# MCED_Controller.net
KiCad netlist of a schematic drawn in Altium Designer
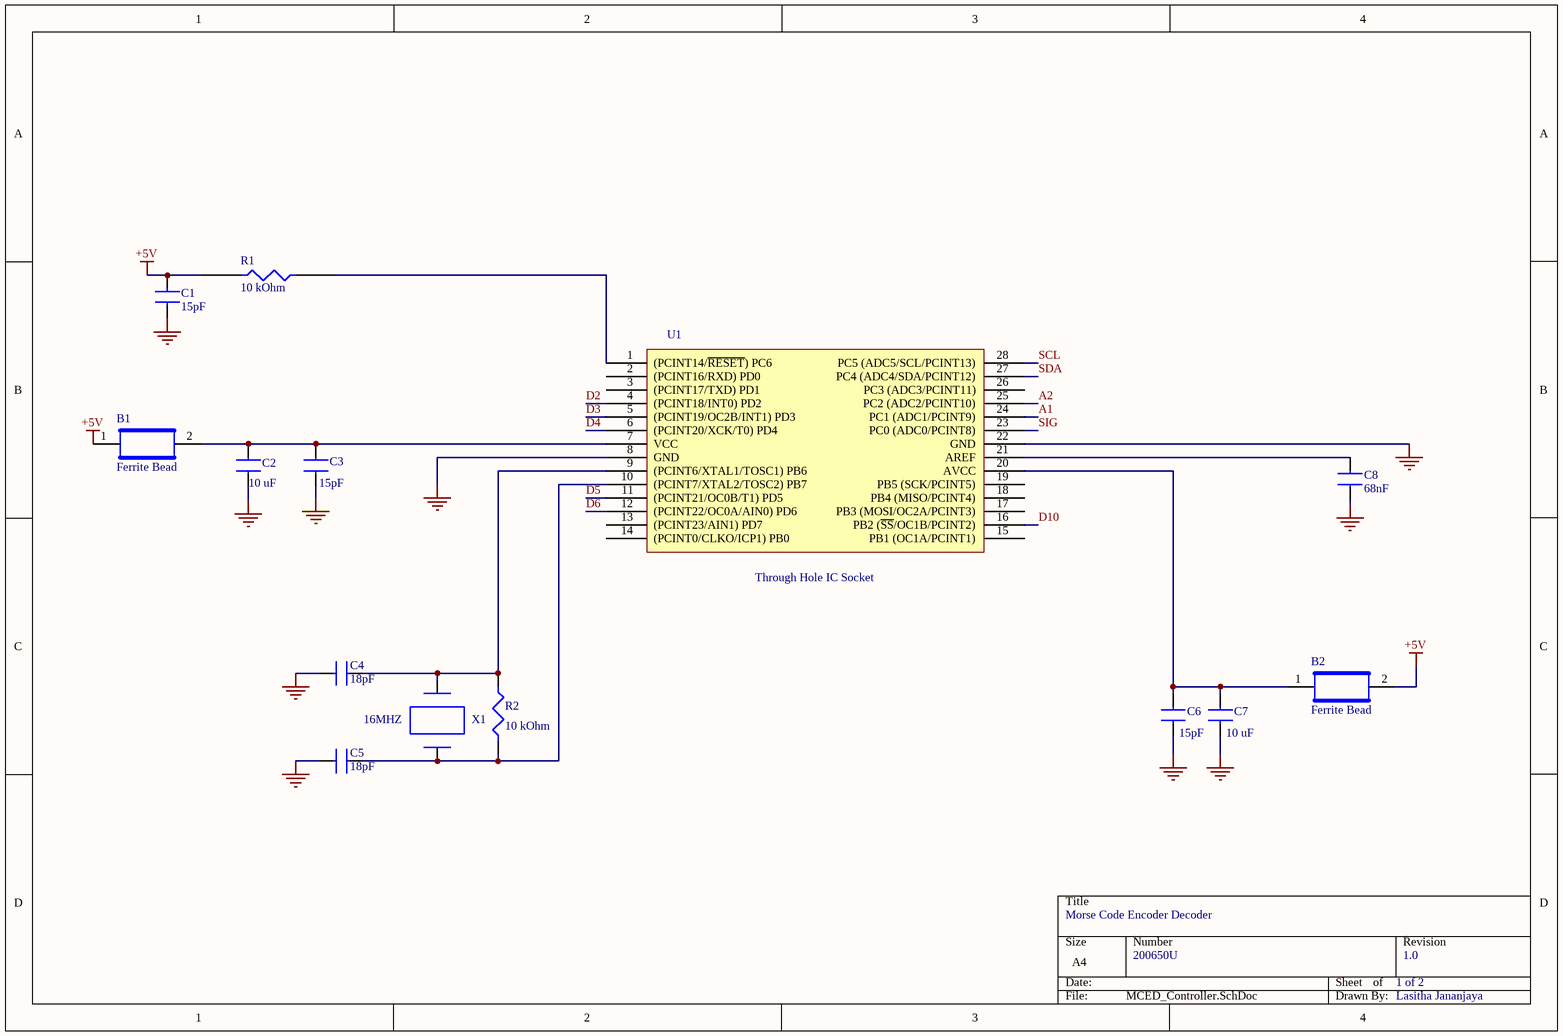
[diagram p0: MCED_Controller.SchDoc]

(export (version "E")
  (design (tool "Eeschema 10.0.6"))
  (components
    (comp (ref "B1")
      (value "Ferrite Bead")
      (footprint "FERRITE BEAD C2012X105N")
      (description "Ferrite Bead, 1 Function(s), 2A")
      (fields
        (field (name "MANUFACTURER") "TDK")
        (field (name "MANUFACTURER PART NUMBER") "MPZ2012S601AT000")
      )
      (libsource (lib "MCED_Schlib") (part "MPZ2012S601AT000"))
    )
    (comp (ref "B2")
      (value "Ferrite Bead")
      (footprint "FERRITE BEAD C2012X105N")
      (description "Ferrite Bead, 1 Function(s), 2A")
      (fields
        (field (name "MANUFACTURER") "TDK")
        (field (name "MANUFACTURER PART NUMBER") "MPZ2012S601AT000")
      )
      (libsource (lib "MCED_Schlib") (part "MPZ2012S601AT000"))
    )
    (comp (ref "C1")
      (value "15pF")
      (footprint "C0805")
      (fields
        (field (name "MANUFACTURER") "Vishay Vitramon")
        (field (name "MANUFACTURER PART NUMBER") "VJ0805A220GXACW1BC")
      )
      (libsource (lib "MCED_Schlib") (part "VJ0805A220GXACW1BC"))
    )
    (comp (ref "C2")
      (value "10 uF")
      (footprint "C0805")
      (fields
        (field (name "MANUFACTURER") "Samsung")
        (field (name "MANUFACTURER PART NUMBER") "CL21A106KBYQNNE")
      )
      (libsource (lib "MCED_Schlib") (part "CL21A106KBYQNNE"))
    )
    (comp (ref "C3")
      (value "15pF")
      (footprint "C0805")
      (fields
        (field (name "MANUFACTURER") "Vishay Vitramon")
        (field (name "MANUFACTURER PART NUMBER") "VJ0805A220GXACW1BC")
      )
      (libsource (lib "MCED_Schlib") (part "VJ0805A220GXACW1BC"))
    )
    (comp (ref "C4")
      (value "18pF")
      (footprint "C0805")
      (fields
        (field (name "MANUFACTURER") "Vishay Vitramon")
        (field (name "MANUFACTURER PART NUMBER") "VJ0805A220GXACW1BC")
      )
      (libsource (lib "MCED_Schlib") (part "VJ0805A220GXACW1BC"))
    )
    (comp (ref "C5")
      (value "18pF")
      (footprint "C0805")
      (fields
        (field (name "MANUFACTURER") "Vishay Vitramon")
        (field (name "MANUFACTURER PART NUMBER") "VJ0805A220GXACW1BC")
      )
      (libsource (lib "MCED_Schlib") (part "VJ0805A220GXACW1BC"))
    )
    (comp (ref "C6")
      (value "15pF")
      (footprint "C0805")
      (fields
        (field (name "MANUFACTURER") "Vishay Vitramon")
        (field (name "MANUFACTURER PART NUMBER") "VJ0805A220GXACW1BC")
      )
      (libsource (lib "MCED_Schlib") (part "VJ0805A220GXACW1BC"))
    )
    (comp (ref "C7")
      (value "10 uF")
      (footprint "C0805")
      (fields
        (field (name "MANUFACTURER") "Samsung")
        (field (name "MANUFACTURER PART NUMBER") "CL21A106KBYQNNE")
      )
      (libsource (lib "MCED_Schlib") (part "CL21A106KBYQNNE"))
    )
    (comp (ref "C8")
      (value "68nF")
      (footprint "C0805")
      (fields
        (field (name "MANUFACTURER") "Samsung")
        (field (name "MANUFACTURER PART NUMBER") "CL21A106KBYQNNE")
      )
      (libsource (lib "MCED_Schlib") (part "CL21A106KBYQNNE"))
    )
    (comp (ref "R1")
      (value "10 kOhm")
      (footprint "10K")
      (description "10 kOhm, Fixed Resistor, Thin Film, 0.2W, 10000ohm, 150V, 0.5% +/-Tol, -25,25ppm/Cel, 0805")
      (fields
        (field (name "MANUFACTURER") "Vishay Beyschlag")
        (field (name "MANUFACTURER PART NUMBER") "MCU0805MD1002DP500")
      )
      (libsource (lib "") (part "MCU0805MD1002DP500_1"))
    )
    (comp (ref "R2")
      (value "10 kOhm")
      (footprint "10K")
      (description "10 kOhm, Fixed Resistor, Thin Film, 0.2W, 10000ohm, 150V, 0.5% +/-Tol, -25,25ppm/Cel, 0805")
      (fields
        (field (name "MANUFACTURER") "Vishay Beyschlag")
        (field (name "MANUFACTURER PART NUMBER") "MCU0805MD1002DP500")
      )
      (libsource (lib "MCED_Schlib") (part "MCU0805MD1002DP500"))
    )
    (comp (ref "U1")
      (value "Through Hole IC Socket")
      (footprint "28dip_through_hole_ic_socket")
      (description "Through Hole IC Sockets 28P / .300\"")
      (fields
        (field (name "MANUFACTURER") "Adam Equipment")
        (field (name "MANUFACTURER PART NUMBER") "ICS-328-T")
      )
      (libsource (lib "MCED_Schlib") (part "ICS-328-T"))
    )
    (comp (ref "X1")
      (value "16MHZ")
      (footprint "ABLS-16.000MHZ-B4-T_CRYSTAL")
      (description "16MHz ±30ppm 晶体 18pF 40 欧姆 -20°C ~ 70°C  表面贴装 HC49/US")
      (fields
        (field (name "MANUFACTURER") "Abracon")
        (field (name "MANUFACTURER PART NUMBER") "ABLS-16.000MHZ-B4-T")
      )
      (libsource (lib "MCED_Schlib") (part "ABLS-16.000MHZ-B4-T"))
    )
  )
  (nets
    (net (code "1") (name "+5V") (class "Default")
      (node (ref "B1") (pin "1") (pinfunction "1_1") (pintype "passive"))
      (node (ref "B2") (pin "2") (pinfunction "2_2") (pintype "passive"))
      (node (ref "C1") (pin "2") (pinfunction "2_2") (pintype "passive"))
      (node (ref "R1") (pin "2") (pinfunction "2_2") (pintype "passive"))
    )
    (net (code "2") (name "/A1") (class "Default")
      (node (ref "U1") (pin "24") (pinfunction "PC1_(ADC1/PCINT9)_24") (pintype "passive"))
    )
    (net (code "3") (name "/A2") (class "Default")
      (node (ref "U1") (pin "25") (pinfunction "PC2_(ADC2/PCINT10)_25") (pintype "passive"))
    )
    (net (code "4") (name "/D2") (class "Default")
      (node (ref "U1") (pin "4") (pinfunction "(PCINT18/INT0)_PD2_4") (pintype "passive"))
    )
    (net (code "5") (name "/D3") (class "Default")
      (node (ref "U1") (pin "5") (pinfunction "(PCINT19/OC2B/INT1)_PD3_5") (pintype "passive"))
    )
    (net (code "6") (name "/D4") (class "Default")
      (node (ref "U1") (pin "6") (pinfunction "(PCINT20/XCK/T0)_PD4_6") (pintype "passive"))
    )
    (net (code "7") (name "/D5") (class "Default")
      (node (ref "U1") (pin "11") (pinfunction "(PCINT21/OC0B/T1)_PD5_11") (pintype "passive"))
    )
    (net (code "8") (name "/D6") (class "Default")
      (node (ref "U1") (pin "12") (pinfunction "(PCINT22/OC0A/AIN0)_PD6_12") (pintype "passive"))
    )
    (net (code "9") (name "/D10") (class "Default")
      (node (ref "U1") (pin "16") (pinfunction "PB2_(~{SS}/OC1B/PCINT2)_16") (pintype "passive"))
    )
    (net (code "10") (name "/SCL") (class "Default")
      (node (ref "U1") (pin "28") (pinfunction "PC5_(ADC5/SCL/PCINT13)_28") (pintype "passive"))
    )
    (net (code "11") (name "/SDA") (class "Default")
      (node (ref "U1") (pin "27") (pinfunction "PC4_(ADC4/SDA/PCINT12)_27") (pintype "passive"))
    )
    (net (code "12") (name "/SIG") (class "Default")
      (node (ref "U1") (pin "23") (pinfunction "PC0_(ADC0/PCINT8)_23") (pintype "passive"))
    )
    (net (code "13") (name "GND") (class "Default")
      (node (ref "C1") (pin "1") (pinfunction "1_1") (pintype "passive"))
      (node (ref "C2") (pin "1") (pinfunction "1_1") (pintype "passive"))
      (node (ref "C3") (pin "1") (pinfunction "1_1") (pintype "passive"))
      (node (ref "C4") (pin "2") (pinfunction "2_2") (pintype "passive"))
      (node (ref "C5") (pin "2") (pinfunction "2_2") (pintype "passive"))
      (node (ref "C6") (pin "1") (pinfunction "1_1") (pintype "passive"))
      (node (ref "C7") (pin "1") (pinfunction "1_1") (pintype "passive"))
      (node (ref "C8") (pin "1") (pinfunction "1_1") (pintype "passive"))
      (node (ref "U1") (pin "22") (pinfunction "GND_22") (pintype "passive"))
      (node (ref "U1") (pin "8") (pinfunction "GND_8") (pintype "passive"))
    )
    (net (code "14") (name "Net-(U1-(PCINT6{slash}XTAL1{slash}TOSC1)_PB6)") (class "Default")
      (node (ref "C4") (pin "1") (pinfunction "1_1") (pintype "passive"))
      (node (ref "R2") (pin "2") (pinfunction "2_2") (pintype "passive"))
      (node (ref "U1") (pin "9") (pinfunction "(PCINT6/XTAL1/TOSC1)_PB6_9") (pintype "passive"))
      (node (ref "X1") (pin "2") (pinfunction "2_2") (pintype "passive"))
    )
    (net (code "15") (name "Net-(U1-(PCINT7{slash}XTAL2{slash}TOSC2)_PB7)") (class "Default")
      (node (ref "C5") (pin "1") (pinfunction "1_1") (pintype "passive"))
      (node (ref "R2") (pin "1") (pinfunction "1_1") (pintype "passive"))
      (node (ref "U1") (pin "10") (pinfunction "(PCINT7/XTAL2/TOSC2)_PB7_10") (pintype "passive"))
      (node (ref "X1") (pin "1") (pinfunction "1_1") (pintype "passive"))
    )
    (net (code "16") (name "Net-(U1-(PCINT14{slash}~{RESET})_PC6)") (class "Default")
      (node (ref "R1") (pin "1") (pinfunction "1_1") (pintype "passive"))
      (node (ref "U1") (pin "1") (pinfunction "(PCINT14/~{RESET})_PC6_1") (pintype "passive"))
    )
    (net (code "17") (name "Net-(U1-AREF)") (class "Default")
      (node (ref "C8") (pin "2") (pinfunction "2_2") (pintype "passive"))
      (node (ref "U1") (pin "21") (pinfunction "AREF_21") (pintype "passive"))
    )
    (net (code "18") (name "Net-(U1-AVCC)") (class "Default")
      (node (ref "B2") (pin "1") (pinfunction "1_1") (pintype "passive"))
      (node (ref "C6") (pin "2") (pinfunction "2_2") (pintype "passive"))
      (node (ref "C7") (pin "2") (pinfunction "2_2") (pintype "passive"))
      (node (ref "U1") (pin "20") (pinfunction "AVCC_20") (pintype "passive"))
    )
    (net (code "19") (name "Net-(U1-VCC)") (class "Default")
      (node (ref "B1") (pin "2") (pinfunction "2_2") (pintype "passive"))
      (node (ref "C2") (pin "2") (pinfunction "2_2") (pintype "passive"))
      (node (ref "C3") (pin "2") (pinfunction "2_2") (pintype "passive"))
      (node (ref "U1") (pin "7") (pinfunction "VCC_7") (pintype "passive"))
    )
    (net (code "20") (name "unconnected-(U1-(PCINT0{slash}CLKO{slash}ICP1)_PB0-Pad14)") (class "Default")
      (node (ref "U1") (pin "14") (pinfunction "(PCINT0/CLKO/ICP1)_PB0_14") (pintype "passive"))
    )
    (net (code "21") (name "unconnected-(U1-(PCINT16{slash}RXD)_PD0-Pad2)") (class "Default")
      (node (ref "U1") (pin "2") (pinfunction "(PCINT16/RXD)_PD0_2") (pintype "passive"))
    )
    (net (code "22") (name "unconnected-(U1-(PCINT17{slash}TXD)_PD1-Pad3)") (class "Default")
      (node (ref "U1") (pin "3") (pinfunction "(PCINT17/TXD)_PD1_3") (pintype "passive"))
    )
    (net (code "23") (name "unconnected-(U1-(PCINT23{slash}AIN1)_PD7-Pad13)") (class "Default")
      (node (ref "U1") (pin "13") (pinfunction "(PCINT23/AIN1)_PD7_13") (pintype "passive"))
    )
    (net (code "24") (name "unconnected-(U1-PB1_(OC1A{slash}PCINT1)-Pad15)") (class "Default")
      (node (ref "U1") (pin "15") (pinfunction "PB1_(OC1A/PCINT1)_15") (pintype "passive"))
    )
    (net (code "25") (name "unconnected-(U1-PB3_(MOSI{slash}OC2A{slash}PCINT3)-Pad17)") (class "Default")
      (node (ref "U1") (pin "17") (pinfunction "PB3_(MOSI/OC2A/PCINT3)_17") (pintype "passive"))
    )
    (net (code "26") (name "unconnected-(U1-PB4_(MISO{slash}PCINT4)-Pad18)") (class "Default")
      (node (ref "U1") (pin "18") (pinfunction "PB4_(MISO/PCINT4)_18") (pintype "passive"))
    )
    (net (code "27") (name "unconnected-(U1-PB5_(SCK{slash}PCINT5)-Pad19)") (class "Default")
      (node (ref "U1") (pin "19") (pinfunction "PB5_(SCK/PCINT5)_19") (pintype "passive"))
    )
    (net (code "28") (name "unconnected-(U1-PC3_(ADC3{slash}PCINT11)-Pad26)") (class "Default")
      (node (ref "U1") (pin "26") (pinfunction "PC3_(ADC3/PCINT11)_26") (pintype "passive"))
    )
  )
)
